# BMS_Slave.net
KiCad netlist of a schematic drawn in Altium Designer
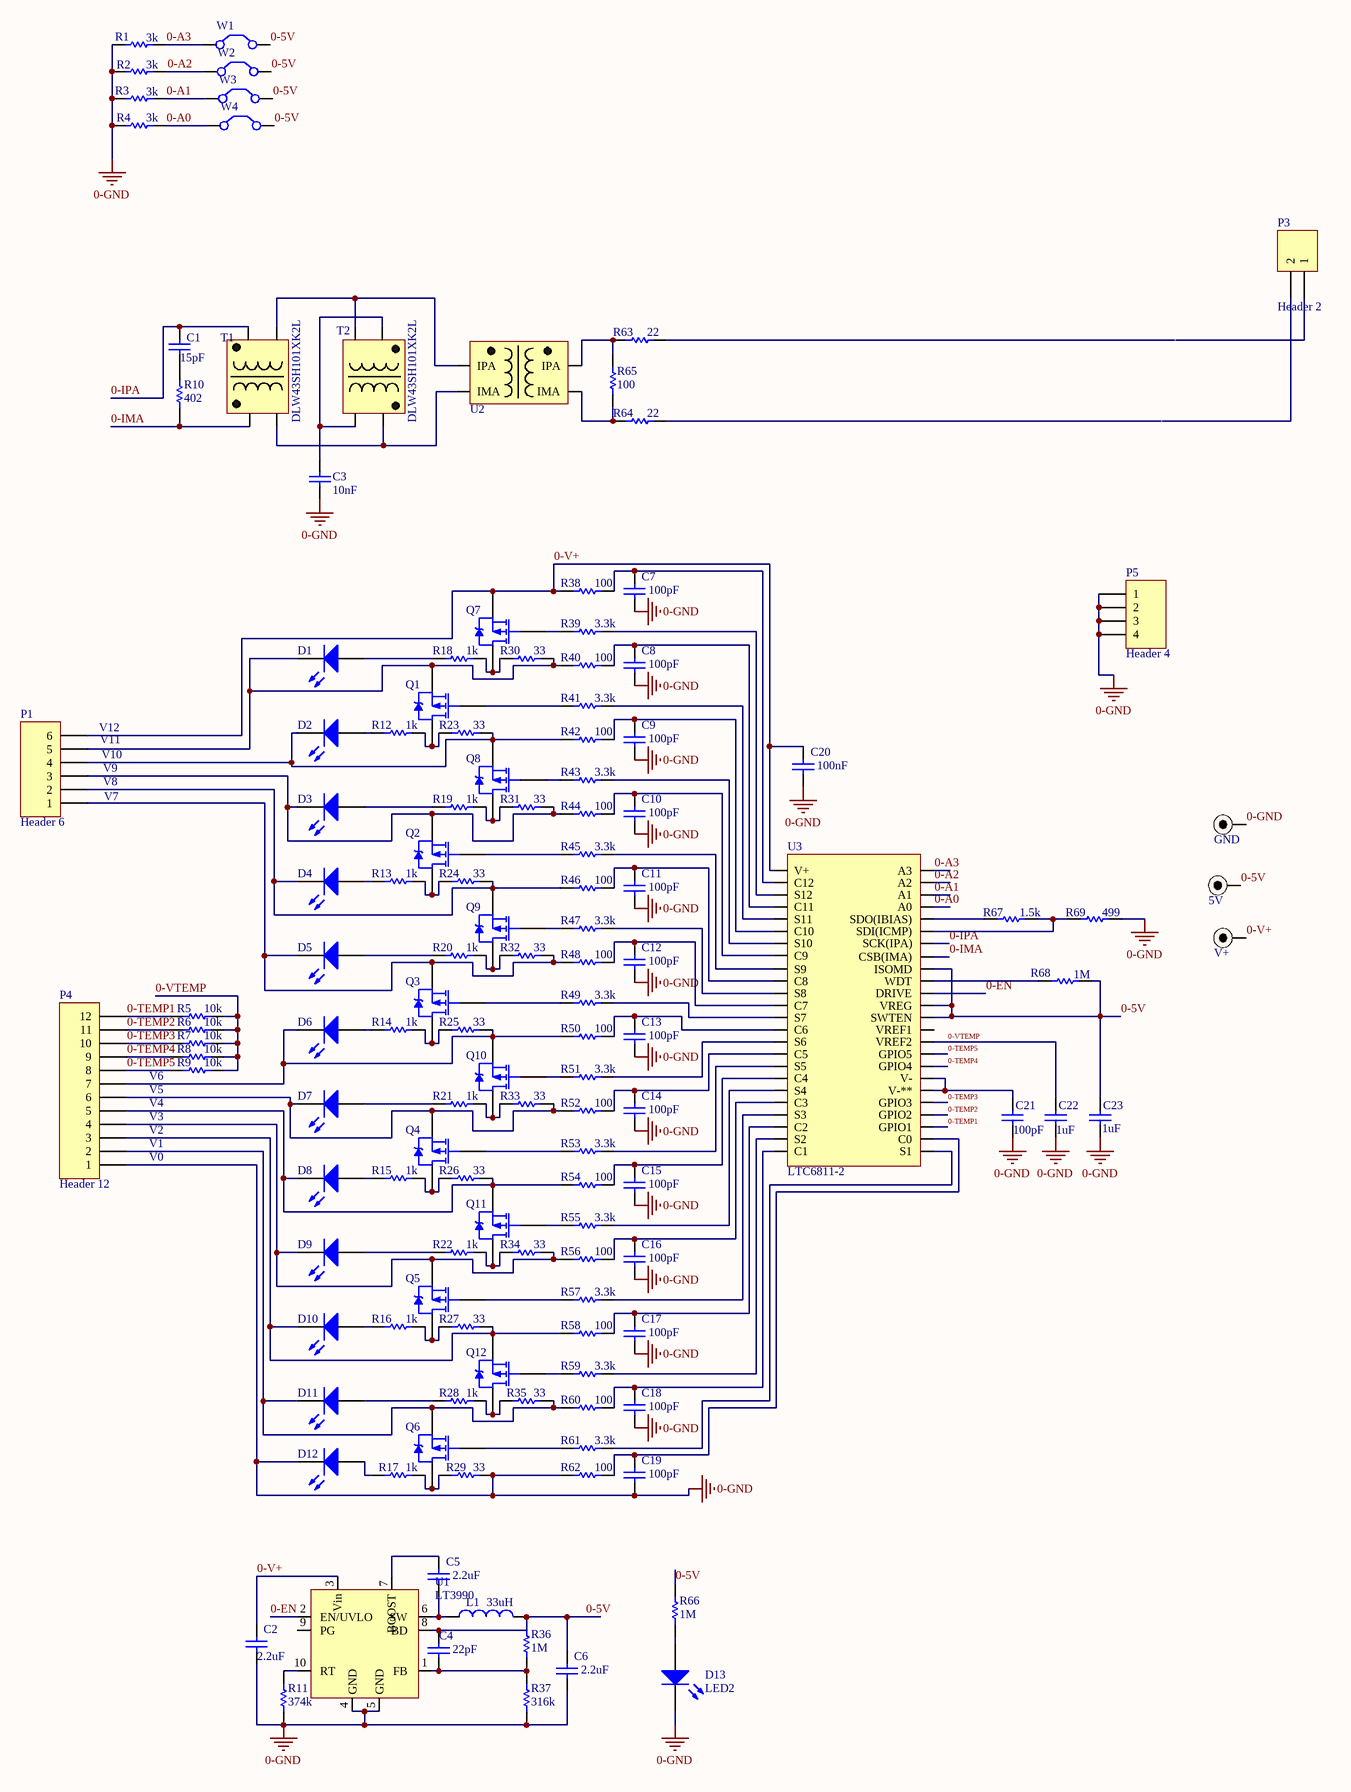
[diagram p0: BMS Slave.SchDoc]

(export (version "E")
  (design (tool "Eeschema 10.0.6"))
  (components
    (comp (ref "5V")
      (value "EXPOSED SOLDER PAD")
      (footprint "TEST PAD")
      (description "testing point")
      (libsource (lib "MFE_temp") (part "EXPOSED SOLDER PAD"))
    )
    (comp (ref "C1")
      (value "15pF")
      (footprint "6-0805_L")
      (description "Capacitor")
      (fields (field (name "Comment") "Cap") (field (name "PUBLISHER") "Altium Limited"))
      (libsource (lib "Miscellaneous Devices") (part "Cap"))
    )
    (comp (ref "C2")
      (value "2.2uF")
      (footprint "6-0805_L")
      (description "Capacitor")
      (fields (field (name "Comment") "Cap") (field (name "PUBLISHER") "Altium Limited"))
      (libsource (lib "Miscellaneous Devices") (part "Cap"))
    )
    (comp (ref "C3")
      (value "10nF")
      (footprint "6-0805_L")
      (description "Capacitor")
      (fields (field (name "Comment") "Cap") (field (name "PUBLISHER") "Altium Limited"))
      (libsource (lib "Miscellaneous Devices") (part "Cap"))
    )
    (comp (ref "C4")
      (value "22pF")
      (footprint "6-0805_L")
      (description "Capacitor")
      (fields (field (name "Comment") "Cap") (field (name "PUBLISHER") "Altium Limited"))
      (libsource (lib "Miscellaneous Devices") (part "Cap"))
    )
    (comp (ref "C5")
      (value "2.2uF")
      (footprint "6-0805_L")
      (description "Capacitor")
      (fields (field (name "Comment") "Cap") (field (name "PUBLISHER") "Altium Limited"))
      (libsource (lib "Miscellaneous Devices") (part "Cap"))
    )
    (comp (ref "C6")
      (value "2.2uF")
      (footprint "6-0805_L")
      (description "Capacitor")
      (fields (field (name "Comment") "Cap") (field (name "PUBLISHER") "Altium Limited"))
      (libsource (lib "Miscellaneous Devices") (part "Cap"))
    )
    (comp (ref "C7")
      (value "100pF")
      (footprint "6-0805_L")
      (description "Capacitor")
      (fields (field (name "Comment") "Cap") (field (name "PUBLISHER") "Altium Limited"))
      (libsource (lib "Miscellaneous Devices") (part "Cap"))
    )
    (comp (ref "C8")
      (value "100pF")
      (footprint "6-0805_L")
      (description "Capacitor")
      (fields (field (name "Comment") "Cap") (field (name "PUBLISHER") "Altium Limited"))
      (libsource (lib "Miscellaneous Devices") (part "Cap"))
    )
    (comp (ref "C9")
      (value "100pF")
      (footprint "6-0805_L")
      (description "Capacitor")
      (fields (field (name "Comment") "Cap") (field (name "PUBLISHER") "Altium Limited"))
      (libsource (lib "Miscellaneous Devices") (part "Cap"))
    )
    (comp (ref "C10")
      (value "100pF")
      (footprint "6-0805_L")
      (description "Capacitor")
      (fields (field (name "Comment") "Cap") (field (name "PUBLISHER") "Altium Limited"))
      (libsource (lib "Miscellaneous Devices") (part "Cap"))
    )
    (comp (ref "C11")
      (value "100pF")
      (footprint "6-0805_L")
      (description "Capacitor")
      (fields (field (name "Comment") "Cap") (field (name "PUBLISHER") "Altium Limited"))
      (libsource (lib "Miscellaneous Devices") (part "Cap"))
    )
    (comp (ref "C12")
      (value "100pF")
      (footprint "6-0805_L")
      (description "Capacitor")
      (fields (field (name "Comment") "Cap") (field (name "PUBLISHER") "Altium Limited"))
      (libsource (lib "Miscellaneous Devices") (part "Cap"))
    )
    (comp (ref "C13")
      (value "100pF")
      (footprint "6-0805_L")
      (description "Capacitor")
      (fields (field (name "Comment") "Cap") (field (name "PUBLISHER") "Altium Limited"))
      (libsource (lib "Miscellaneous Devices") (part "Cap"))
    )
    (comp (ref "C14")
      (value "100pF")
      (footprint "6-0805_L")
      (description "Capacitor")
      (fields (field (name "Comment") "Cap") (field (name "PUBLISHER") "Altium Limited"))
      (libsource (lib "Miscellaneous Devices") (part "Cap"))
    )
    (comp (ref "C15")
      (value "100pF")
      (footprint "6-0805_L")
      (description "Capacitor")
      (fields (field (name "Comment") "Cap") (field (name "PUBLISHER") "Altium Limited"))
      (libsource (lib "Miscellaneous Devices") (part "Cap"))
    )
    (comp (ref "C16")
      (value "100pF")
      (footprint "6-0805_L")
      (description "Capacitor")
      (fields (field (name "Comment") "Cap") (field (name "PUBLISHER") "Altium Limited"))
      (libsource (lib "Miscellaneous Devices") (part "Cap"))
    )
    (comp (ref "C17")
      (value "100pF")
      (footprint "6-0805_L")
      (description "Capacitor")
      (fields (field (name "Comment") "Cap") (field (name "PUBLISHER") "Altium Limited"))
      (libsource (lib "Miscellaneous Devices") (part "Cap"))
    )
    (comp (ref "C18")
      (value "100pF")
      (footprint "6-0805_L")
      (description "Capacitor")
      (fields (field (name "Comment") "Cap") (field (name "PUBLISHER") "Altium Limited"))
      (libsource (lib "Miscellaneous Devices") (part "Cap"))
    )
    (comp (ref "C19")
      (value "100pF")
      (footprint "6-0805_L")
      (description "Capacitor")
      (fields (field (name "Comment") "Cap") (field (name "PUBLISHER") "Altium Limited"))
      (libsource (lib "Miscellaneous Devices") (part "Cap"))
    )
    (comp (ref "C20")
      (value "100nF")
      (footprint "6-0805_L")
      (description "Capacitor")
      (fields (field (name "Comment") "Cap") (field (name "PUBLISHER") "Altium Limited"))
      (libsource (lib "Miscellaneous Devices") (part "Cap"))
    )
    (comp (ref "C21")
      (value "100pF")
      (footprint "6-0805_L")
      (description "Capacitor")
      (fields (field (name "Comment") "Cap") (field (name "PUBLISHER") "Altium Limited"))
      (libsource (lib "Miscellaneous Devices") (part "Cap"))
    )
    (comp (ref "C22")
      (value "1uF")
      (footprint "6-0805_L")
      (description "Capacitor")
      (fields (field (name "Comment") "Cap") (field (name "PUBLISHER") "Altium Limited"))
      (libsource (lib "Miscellaneous Devices") (part "Cap"))
    )
    (comp (ref "C23")
      (value "1uF")
      (footprint "6-0805_L")
      (description "Capacitor")
      (fields (field (name "Comment") "Cap") (field (name "PUBLISHER") "Altium Limited"))
      (libsource (lib "Miscellaneous Devices") (part "Cap"))
    )
    (comp (ref "D1")
      (value "Green LED")
      (footprint "1608[0603]")
      (description "LG L29K-G2J1-24-Z")
      (fields (field (name "PUBLISHER") "Altium Limited"))
      (libsource (lib "Miscellaneous Devices") (part "LED2"))
    )
    (comp (ref "D2")
      (value "Green LED")
      (footprint "1608[0603]")
      (description "LG L29K-G2J1-24-Z")
      (fields (field (name "PUBLISHER") "Altium Limited"))
      (libsource (lib "Miscellaneous Devices") (part "LED2"))
    )
    (comp (ref "D3")
      (value "Green LED")
      (footprint "1608[0603]")
      (description "LG L29K-G2J1-24-Z")
      (fields (field (name "PUBLISHER") "Altium Limited"))
      (libsource (lib "Miscellaneous Devices") (part "LED2"))
    )
    (comp (ref "D4")
      (value "Green LED")
      (footprint "1608[0603]")
      (description "LG L29K-G2J1-24-Z")
      (fields (field (name "PUBLISHER") "Altium Limited"))
      (libsource (lib "Miscellaneous Devices") (part "LED2"))
    )
    (comp (ref "D5")
      (value "Green LED")
      (footprint "1608[0603]")
      (description "LG L29K-G2J1-24-Z")
      (fields (field (name "PUBLISHER") "Altium Limited"))
      (libsource (lib "Miscellaneous Devices") (part "LED2"))
    )
    (comp (ref "D6")
      (value "Green LED")
      (footprint "1608[0603]")
      (description "LG L29K-G2J1-24-Z")
      (fields (field (name "PUBLISHER") "Altium Limited"))
      (libsource (lib "Miscellaneous Devices") (part "LED2"))
    )
    (comp (ref "D7")
      (value "Green LED")
      (footprint "1608[0603]")
      (description "LG L29K-G2J1-24-Z")
      (fields (field (name "PUBLISHER") "Altium Limited"))
      (libsource (lib "Miscellaneous Devices") (part "LED2"))
    )
    (comp (ref "D8")
      (value "Green LED")
      (footprint "1608[0603]")
      (description "LG L29K-G2J1-24-Z")
      (fields (field (name "PUBLISHER") "Altium Limited"))
      (libsource (lib "Miscellaneous Devices") (part "LED2"))
    )
    (comp (ref "D9")
      (value "Green LED")
      (footprint "1608[0603]")
      (description "LG L29K-G2J1-24-Z")
      (fields (field (name "PUBLISHER") "Altium Limited"))
      (libsource (lib "Miscellaneous Devices") (part "LED2"))
    )
    (comp (ref "D10")
      (value "Green LED")
      (footprint "1608[0603]")
      (description "LG L29K-G2J1-24-Z")
      (fields (field (name "PUBLISHER") "Altium Limited"))
      (libsource (lib "Miscellaneous Devices") (part "LED2"))
    )
    (comp (ref "D11")
      (value "Green LED")
      (footprint "1608[0603]")
      (description "LG L29K-G2J1-24-Z")
      (fields (field (name "PUBLISHER") "Altium Limited"))
      (libsource (lib "Miscellaneous Devices") (part "LED2"))
    )
    (comp (ref "D12")
      (value "Green LED")
      (footprint "1608[0603]")
      (description "LG L29K-G2J1-24-Z")
      (fields (field (name "PUBLISHER") "Altium Limited"))
      (libsource (lib "Miscellaneous Devices") (part "LED2"))
    )
    (comp (ref "D13")
      (value "LED2")
      (footprint "3.2X1.6X1.1")
      (description "Typical RED, GREEN, YELLOW, AMBER GaAs LED")
      (fields (field (name "PUBLISHER") "Altium Limited"))
      (libsource (lib "Miscellaneous Devices") (part "LED2"))
    )
    (comp (ref "GND")
      (value "EXPOSED SOLDER PAD")
      (footprint "TEST PAD")
      (description "testing point")
      (libsource (lib "MFE_temp") (part "EXPOSED SOLDER PAD"))
    )
    (comp (ref "L1")
      (value "33uH")
      (footprint "0402-A")
      (description "Inductor")
      (fields (field (name "PUBLISHER") "Altium Limited"))
      (libsource (lib "Miscellaneous Devices") (part "Inductor"))
    )
    (comp (ref "P1")
      (value "Header 6")
      (footprint "HDR2X3_CEN")
      (description "Header, 6-Pin")
      (fields (field (name "PUBLISHER") "Altium Limited"))
      (libsource (lib "Miscellaneous Connectors") (part "Header 6"))
    )
    (comp (ref "P3")
      (value "Header 2")
      (footprint "MOLEX MICROCLASP 2POS RIGHT ANGLE")
      (description "Header, 2-Pin")
      (fields (field (name "PUBLISHER") "Altium Limited"))
      (libsource (lib "Miscellaneous Connectors") (part "Header 2"))
    )
    (comp (ref "P4")
      (value "Header 12")
      (footprint "HDR2X6")
      (description "Header, 12-Pin")
      (fields (field (name "PUBLISHER") "Altium Limited"))
      (libsource (lib "Miscellaneous Connectors") (part "Header 12"))
    )
    (comp (ref "P5")
      (value "Header 4")
      (footprint "HDR2X2")
      (description "Header, 4-Pin")
      (fields (field (name "PUBLISHER") "Altium Limited"))
      (libsource (lib "Miscellaneous Connectors") (part "Header 4"))
    )
    (comp (ref "Q1")
      (value "SI2347DS-T1-GE3")
      (footprint "SOT23-3N")
      (description "MOSFET P-CH 30V 5A SOT-23")
      (fields (field (name "PUBLISHER") "Altium Limited"))
      (libsource (lib "Miscellaneous Devices") (part "PMOS-2"))
    )
    (comp (ref "Q2")
      (value "SI2347DS-T1-GE3")
      (footprint "SOT23-3N")
      (description "MOSFET P-CH 30V 5A SOT-23")
      (fields (field (name "PUBLISHER") "Altium Limited"))
      (libsource (lib "Miscellaneous Devices") (part "PMOS-2"))
    )
    (comp (ref "Q3")
      (value "SI2347DS-T1-GE3")
      (footprint "SOT23-3N")
      (description "MOSFET P-CH 30V 5A SOT-23")
      (fields (field (name "PUBLISHER") "Altium Limited"))
      (libsource (lib "Miscellaneous Devices") (part "PMOS-2"))
    )
    (comp (ref "Q4")
      (value "SI2347DS-T1-GE3")
      (footprint "SOT23-3N")
      (description "MOSFET P-CH 30V 5A SOT-23")
      (fields (field (name "PUBLISHER") "Altium Limited"))
      (libsource (lib "Miscellaneous Devices") (part "PMOS-2"))
    )
    (comp (ref "Q5")
      (value "SI2347DS-T1-GE3")
      (footprint "SOT23-3N")
      (description "MOSFET P-CH 30V 5A SOT-23")
      (fields (field (name "PUBLISHER") "Altium Limited"))
      (libsource (lib "Miscellaneous Devices") (part "PMOS-2"))
    )
    (comp (ref "Q6")
      (value "SI2347DS-T1-GE3")
      (footprint "SOT23-3N")
      (description "MOSFET P-CH 30V 5A SOT-23")
      (fields (field (name "PUBLISHER") "Altium Limited"))
      (libsource (lib "Miscellaneous Devices") (part "PMOS-2"))
    )
    (comp (ref "Q7")
      (value "SI2347DS-T1-GE3")
      (footprint "SOT23-3N")
      (description "MOSFET P-CH 30V 5A SOT-23")
      (fields (field (name "PUBLISHER") "Altium Limited"))
      (libsource (lib "Miscellaneous Devices") (part "PMOS-2"))
    )
    (comp (ref "Q8")
      (value "SI2347DS-T1-GE3")
      (footprint "SOT23-3N")
      (description "MOSFET P-CH 30V 5A SOT-23")
      (fields (field (name "PUBLISHER") "Altium Limited"))
      (libsource (lib "Miscellaneous Devices") (part "PMOS-2"))
    )
    (comp (ref "Q9")
      (value "SI2347DS-T1-GE3")
      (footprint "SOT23-3N")
      (description "MOSFET P-CH 30V 5A SOT-23")
      (fields (field (name "PUBLISHER") "Altium Limited"))
      (libsource (lib "Miscellaneous Devices") (part "PMOS-2"))
    )
    (comp (ref "Q10")
      (value "SI2347DS-T1-GE3")
      (footprint "SOT23-3N")
      (description "MOSFET P-CH 30V 5A SOT-23")
      (fields (field (name "PUBLISHER") "Altium Limited"))
      (libsource (lib "Miscellaneous Devices") (part "PMOS-2"))
    )
    (comp (ref "Q11")
      (value "SI2347DS-T1-GE3")
      (footprint "SOT23-3N")
      (description "MOSFET P-CH 30V 5A SOT-23")
      (fields (field (name "PUBLISHER") "Altium Limited"))
      (libsource (lib "Miscellaneous Devices") (part "PMOS-2"))
    )
    (comp (ref "Q12")
      (value "SI2347DS-T1-GE3")
      (footprint "SOT23-3N")
      (description "MOSFET P-CH 30V 5A SOT-23")
      (fields (field (name "PUBLISHER") "Altium Limited"))
      (libsource (lib "Miscellaneous Devices") (part "PMOS-2"))
    )
    (comp (ref "R1")
      (value "3k")
      (footprint "6-0805_L")
      (description "Resistor")
      (fields (field (name "Comment") "Res1") (field (name "PUBLISHER") "Altium Limited"))
      (libsource (lib "Miscellaneous Devices") (part "Res1"))
    )
    (comp (ref "R2")
      (value "3k")
      (footprint "6-0805_L")
      (description "Resistor")
      (fields (field (name "Comment") "Res1") (field (name "PUBLISHER") "Altium Limited"))
      (libsource (lib "Miscellaneous Devices") (part "Res1"))
    )
    (comp (ref "R3")
      (value "3k")
      (footprint "6-0805_L")
      (description "Resistor")
      (fields (field (name "Comment") "Res1") (field (name "PUBLISHER") "Altium Limited"))
      (libsource (lib "Miscellaneous Devices") (part "Res1"))
    )
    (comp (ref "R4")
      (value "3k")
      (footprint "6-0805_L")
      (description "Resistor")
      (fields (field (name "Comment") "Res1") (field (name "PUBLISHER") "Altium Limited"))
      (libsource (lib "Miscellaneous Devices") (part "Res1"))
    )
    (comp (ref "R5")
      (value "10k")
      (footprint "6-0805_L")
      (description "Resistor")
      (fields (field (name "Comment") "Res1") (field (name "PUBLISHER") "Altium Limited"))
      (libsource (lib "Miscellaneous Devices") (part "Res1"))
    )
    (comp (ref "R6")
      (value "10k")
      (footprint "6-0805_L")
      (description "Resistor")
      (fields (field (name "Comment") "Res1") (field (name "PUBLISHER") "Altium Limited"))
      (libsource (lib "Miscellaneous Devices") (part "Res1"))
    )
    (comp (ref "R7")
      (value "10k")
      (footprint "6-0805_L")
      (description "Resistor")
      (fields (field (name "Comment") "Res1") (field (name "PUBLISHER") "Altium Limited"))
      (libsource (lib "Miscellaneous Devices") (part "Res1"))
    )
    (comp (ref "R8")
      (value "10k")
      (footprint "6-0805_L")
      (description "Resistor")
      (fields (field (name "Comment") "Res1") (field (name "PUBLISHER") "Altium Limited"))
      (libsource (lib "Miscellaneous Devices") (part "Res1"))
    )
    (comp (ref "R9")
      (value "10k")
      (footprint "6-0805_L")
      (description "Resistor")
      (fields (field (name "Comment") "Res1") (field (name "PUBLISHER") "Altium Limited"))
      (libsource (lib "Miscellaneous Devices") (part "Res1"))
    )
    (comp (ref "R10")
      (value "402")
      (footprint "6-0805_L")
      (description "Resistor")
      (fields (field (name "Comment") "Res1") (field (name "PUBLISHER") "Altium Limited"))
      (libsource (lib "Miscellaneous Devices") (part "Res1"))
    )
    (comp (ref "R11")
      (value "374k")
      (footprint "6-0805_L")
      (description "Resistor")
      (fields (field (name "Comment") "Res1") (field (name "PUBLISHER") "Altium Limited"))
      (libsource (lib "Miscellaneous Devices") (part "Res1"))
    )
    (comp (ref "R12")
      (value "1k")
      (footprint "1608[0603]")
      (description "Current Limiting Resistor for Green LED")
      (fields (field (name "Comment") "ESR03EZPJ102") (field (name "PUBLISHER") "Altium Limited"))
      (libsource (lib "Miscellaneous Devices") (part "Res1"))
    )
    (comp (ref "R13")
      (value "1k")
      (footprint "1608[0603]")
      (description "Current Limiting Resistor for Green LED")
      (fields (field (name "Comment") "ESR03EZPJ102") (field (name "PUBLISHER") "Altium Limited"))
      (libsource (lib "Miscellaneous Devices") (part "Res1"))
    )
    (comp (ref "R14")
      (value "1k")
      (footprint "1608[0603]")
      (description "Current Limiting Resistor for Green LED")
      (fields (field (name "Comment") "ESR03EZPJ102") (field (name "PUBLISHER") "Altium Limited"))
      (libsource (lib "Miscellaneous Devices") (part "Res1"))
    )
    (comp (ref "R15")
      (value "1k")
      (footprint "1608[0603]")
      (description "Current Limiting Resistor for Green LED")
      (fields (field (name "Comment") "ESR03EZPJ102") (field (name "PUBLISHER") "Altium Limited"))
      (libsource (lib "Miscellaneous Devices") (part "Res1"))
    )
    (comp (ref "R16")
      (value "1k")
      (footprint "1608[0603]")
      (description "Current Limiting Resistor for Green LED")
      (fields (field (name "Comment") "ESR03EZPJ102") (field (name "PUBLISHER") "Altium Limited"))
      (libsource (lib "Miscellaneous Devices") (part "Res1"))
    )
    (comp (ref "R17")
      (value "1k")
      (footprint "1608[0603]")
      (description "Current Limiting Resistor for Green LED")
      (fields (field (name "Comment") "ESR03EZPJ102") (field (name "PUBLISHER") "Altium Limited"))
      (libsource (lib "Miscellaneous Devices") (part "Res1"))
    )
    (comp (ref "R18")
      (value "1k")
      (footprint "1608[0603]")
      (description "Current Limiting Resistor for Green LED")
      (fields (field (name "Comment") "ESR03EZPJ102") (field (name "PUBLISHER") "Altium Limited"))
      (libsource (lib "Miscellaneous Devices") (part "Res1"))
    )
    (comp (ref "R19")
      (value "1k")
      (footprint "1608[0603]")
      (description "Current Limiting Resistor for Green LED")
      (fields (field (name "Comment") "ESR03EZPJ102") (field (name "PUBLISHER") "Altium Limited"))
      (libsource (lib "Miscellaneous Devices") (part "Res1"))
    )
    (comp (ref "R20")
      (value "1k")
      (footprint "1608[0603]")
      (description "Current Limiting Resistor for Green LED")
      (fields (field (name "Comment") "ESR03EZPJ102") (field (name "PUBLISHER") "Altium Limited"))
      (libsource (lib "Miscellaneous Devices") (part "Res1"))
    )
    (comp (ref "R21")
      (value "1k")
      (footprint "1608[0603]")
      (description "Current Limiting Resistor for Green LED")
      (fields (field (name "Comment") "ESR03EZPJ102") (field (name "PUBLISHER") "Altium Limited"))
      (libsource (lib "Miscellaneous Devices") (part "Res1"))
    )
    (comp (ref "R22")
      (value "1k")
      (footprint "1608[0603]")
      (description "Current Limiting Resistor for Green LED")
      (fields (field (name "Comment") "ESR03EZPJ102") (field (name "PUBLISHER") "Altium Limited"))
      (libsource (lib "Miscellaneous Devices") (part "Res1"))
    )
    (comp (ref "R23")
      (value "33")
      (footprint "RES_4122")
      (description "Resistor")
      (fields (field (name "Comment") "Res1") (field (name "PUBLISHER") "Altium Limited"))
      (libsource (lib "Miscellaneous Devices") (part "Res1"))
    )
    (comp (ref "R24")
      (value "33")
      (footprint "RES_4122")
      (description "Resistor")
      (fields (field (name "Comment") "Res1") (field (name "PUBLISHER") "Altium Limited"))
      (libsource (lib "Miscellaneous Devices") (part "Res1"))
    )
    (comp (ref "R25")
      (value "33")
      (footprint "RES_4122")
      (description "Resistor")
      (fields (field (name "Comment") "Res1") (field (name "PUBLISHER") "Altium Limited"))
      (libsource (lib "Miscellaneous Devices") (part "Res1"))
    )
    (comp (ref "R26")
      (value "33")
      (footprint "RES_4122")
      (description "Resistor")
      (fields (field (name "Comment") "Res1") (field (name "PUBLISHER") "Altium Limited"))
      (libsource (lib "Miscellaneous Devices") (part "Res1"))
    )
    (comp (ref "R27")
      (value "33")
      (footprint "RES_4122")
      (description "Resistor")
      (fields (field (name "Comment") "Res1") (field (name "PUBLISHER") "Altium Limited"))
      (libsource (lib "Miscellaneous Devices") (part "Res1"))
    )
    (comp (ref "R28")
      (value "1k")
      (footprint "1608[0603]")
      (description "Current Limiting Resistor for Green LED")
      (fields (field (name "Comment") "ESR03EZPJ102") (field (name "PUBLISHER") "Altium Limited"))
      (libsource (lib "Miscellaneous Devices") (part "Res1"))
    )
    (comp (ref "R29")
      (value "33")
      (footprint "RES_4122")
      (description "Resistor")
      (fields (field (name "Comment") "Res1") (field (name "PUBLISHER") "Altium Limited"))
      (libsource (lib "Miscellaneous Devices") (part "Res1"))
    )
    (comp (ref "R30")
      (value "33")
      (footprint "RES_4122")
      (description "Resistor")
      (fields (field (name "Comment") "Res1") (field (name "PUBLISHER") "Altium Limited"))
      (libsource (lib "Miscellaneous Devices") (part "Res1"))
    )
    (comp (ref "R31")
      (value "33")
      (footprint "RES_4122")
      (description "Resistor")
      (fields (field (name "Comment") "Res1") (field (name "PUBLISHER") "Altium Limited"))
      (libsource (lib "Miscellaneous Devices") (part "Res1"))
    )
    (comp (ref "R32")
      (value "33")
      (footprint "RES_4122")
      (description "Resistor")
      (fields (field (name "Comment") "Res1") (field (name "PUBLISHER") "Altium Limited"))
      (libsource (lib "Miscellaneous Devices") (part "Res1"))
    )
    (comp (ref "R33")
      (value "33")
      (footprint "RES_4122")
      (description "Resistor")
      (fields (field (name "Comment") "Res1") (field (name "PUBLISHER") "Altium Limited"))
      (libsource (lib "Miscellaneous Devices") (part "Res1"))
    )
    (comp (ref "R34")
      (value "33")
      (footprint "RES_4122")
      (description "Resistor")
      (fields (field (name "Comment") "Res1") (field (name "PUBLISHER") "Altium Limited"))
      (libsource (lib "Miscellaneous Devices") (part "Res1"))
    )
    (comp (ref "R35")
      (value "33")
      (footprint "RES_4122")
      (description "Resistor")
      (fields (field (name "Comment") "Res1") (field (name "PUBLISHER") "Altium Limited"))
      (libsource (lib "Miscellaneous Devices") (part "Res1"))
    )
    (comp (ref "R36")
      (value "1M")
      (footprint "6-0805_L")
      (description "Resistor")
      (fields (field (name "Comment") "Res1") (field (name "PUBLISHER") "Altium Limited"))
      (libsource (lib "Miscellaneous Devices") (part "Res1"))
    )
    (comp (ref "R37")
      (value "316k")
      (footprint "6-0805_L")
      (description "Resistor")
      (fields (field (name "Comment") "Res1") (field (name "PUBLISHER") "Altium Limited"))
      (libsource (lib "Miscellaneous Devices") (part "Res1"))
    )
    (comp (ref "R38")
      (value "100")
      (footprint "6-0805_L")
      (description "Resistor")
      (fields (field (name "Comment") "Res1") (field (name "PUBLISHER") "Altium Limited"))
      (libsource (lib "Miscellaneous Devices") (part "Res1"))
    )
    (comp (ref "R39")
      (value "3.3k")
      (footprint "6-0805_L")
      (description "Resistor")
      (fields (field (name "Comment") "Res1") (field (name "PUBLISHER") "Altium Limited"))
      (libsource (lib "Miscellaneous Devices") (part "Res1"))
    )
    (comp (ref "R40")
      (value "100")
      (footprint "6-0805_L")
      (description "Resistor")
      (fields (field (name "Comment") "Res1") (field (name "PUBLISHER") "Altium Limited"))
      (libsource (lib "Miscellaneous Devices") (part "Res1"))
    )
    (comp (ref "R41")
      (value "3.3k")
      (footprint "6-0805_L")
      (description "Resistor")
      (fields (field (name "Comment") "Res1") (field (name "PUBLISHER") "Altium Limited"))
      (libsource (lib "Miscellaneous Devices") (part "Res1"))
    )
    (comp (ref "R42")
      (value "100")
      (footprint "6-0805_L")
      (description "Resistor")
      (fields (field (name "Comment") "Res1") (field (name "PUBLISHER") "Altium Limited"))
      (libsource (lib "Miscellaneous Devices") (part "Res1"))
    )
    (comp (ref "R43")
      (value "3.3k")
      (footprint "6-0805_L")
      (description "Resistor")
      (fields (field (name "Comment") "Res1") (field (name "PUBLISHER") "Altium Limited"))
      (libsource (lib "Miscellaneous Devices") (part "Res1"))
    )
    (comp (ref "R44")
      (value "100")
      (footprint "6-0805_L")
      (description "Resistor")
      (fields (field (name "Comment") "Res1") (field (name "PUBLISHER") "Altium Limited"))
      (libsource (lib "Miscellaneous Devices") (part "Res1"))
    )
    (comp (ref "R45")
      (value "3.3k")
      (footprint "6-0805_L")
      (description "Resistor")
      (fields (field (name "Comment") "Res1") (field (name "PUBLISHER") "Altium Limited"))
      (libsource (lib "Miscellaneous Devices") (part "Res1"))
    )
    (comp (ref "R46")
      (value "100")
      (footprint "6-0805_L")
      (description "Resistor")
      (fields (field (name "Comment") "Res1") (field (name "PUBLISHER") "Altium Limited"))
      (libsource (lib "Miscellaneous Devices") (part "Res1"))
    )
    (comp (ref "R47")
      (value "3.3k")
      (footprint "6-0805_L")
      (description "Resistor")
      (fields (field (name "Comment") "Res1") (field (name "PUBLISHER") "Altium Limited"))
      (libsource (lib "Miscellaneous Devices") (part "Res1"))
    )
    (comp (ref "R48")
      (value "100")
      (footprint "6-0805_L")
      (description "Resistor")
      (fields (field (name "Comment") "Res1") (field (name "PUBLISHER") "Altium Limited"))
      (libsource (lib "Miscellaneous Devices") (part "Res1"))
    )
    (comp (ref "R49")
      (value "3.3k")
      (footprint "6-0805_L")
      (description "Resistor")
      (fields (field (name "Comment") "Res1") (field (name "PUBLISHER") "Altium Limited"))
      (libsource (lib "Miscellaneous Devices") (part "Res1"))
    )
    (comp (ref "R50")
      (value "100")
      (footprint "6-0805_L")
      (description "Resistor")
      (fields (field (name "Comment") "Res1") (field (name "PUBLISHER") "Altium Limited"))
      (libsource (lib "Miscellaneous Devices") (part "Res1"))
    )
    (comp (ref "R51")
      (value "3.3k")
      (footprint "6-0805_L")
      (description "Resistor")
      (fields (field (name "Comment") "Res1") (field (name "PUBLISHER") "Altium Limited"))
      (libsource (lib "Miscellaneous Devices") (part "Res1"))
    )
    (comp (ref "R52")
      (value "100")
      (footprint "6-0805_L")
      (description "Resistor")
      (fields (field (name "Comment") "Res1") (field (name "PUBLISHER") "Altium Limited"))
      (libsource (lib "Miscellaneous Devices") (part "Res1"))
    )
    (comp (ref "R53")
      (value "3.3k")
      (footprint "6-0805_L")
      (description "Resistor")
      (fields (field (name "Comment") "Res1") (field (name "PUBLISHER") "Altium Limited"))
      (libsource (lib "Miscellaneous Devices") (part "Res1"))
    )
    (comp (ref "R54")
      (value "100")
      (footprint "6-0805_L")
      (description "Resistor")
      (fields (field (name "Comment") "Res1") (field (name "PUBLISHER") "Altium Limited"))
      (libsource (lib "Miscellaneous Devices") (part "Res1"))
    )
    (comp (ref "R55")
      (value "3.3k")
      (footprint "6-0805_L")
      (description "Resistor")
      (fields (field (name "Comment") "Res1") (field (name "PUBLISHER") "Altium Limited"))
      (libsource (lib "Miscellaneous Devices") (part "Res1"))
    )
    (comp (ref "R56")
      (value "100")
      (footprint "6-0805_L")
      (description "Resistor")
      (fields (field (name "Comment") "Res1") (field (name "PUBLISHER") "Altium Limited"))
      (libsource (lib "Miscellaneous Devices") (part "Res1"))
    )
    (comp (ref "R57")
      (value "3.3k")
      (footprint "6-0805_L")
      (description "Resistor")
      (fields (field (name "Comment") "Res1") (field (name "PUBLISHER") "Altium Limited"))
      (libsource (lib "Miscellaneous Devices") (part "Res1"))
    )
    (comp (ref "R58")
      (value "100")
      (footprint "6-0805_L")
      (description "Resistor")
      (fields (field (name "Comment") "Res1") (field (name "PUBLISHER") "Altium Limited"))
      (libsource (lib "Miscellaneous Devices") (part "Res1"))
    )
    (comp (ref "R59")
      (value "3.3k")
      (footprint "6-0805_L")
      (description "Resistor")
      (fields (field (name "Comment") "Res1") (field (name "PUBLISHER") "Altium Limited"))
      (libsource (lib "Miscellaneous Devices") (part "Res1"))
    )
    (comp (ref "R60")
      (value "100")
      (footprint "6-0805_L")
      (description "Resistor")
      (fields (field (name "Comment") "Res1") (field (name "PUBLISHER") "Altium Limited"))
      (libsource (lib "Miscellaneous Devices") (part "Res1"))
    )
    (comp (ref "R61")
      (value "3.3k")
      (footprint "6-0805_L")
      (description "Resistor")
      (fields (field (name "Comment") "Res1") (field (name "PUBLISHER") "Altium Limited"))
      (libsource (lib "Miscellaneous Devices") (part "Res1"))
    )
    (comp (ref "R62")
      (value "100")
      (footprint "6-0805_L")
      (description "Resistor")
      (fields (field (name "Comment") "Res1") (field (name "PUBLISHER") "Altium Limited"))
      (libsource (lib "Miscellaneous Devices") (part "Res1"))
    )
    (comp (ref "R63")
      (value "22")
      (footprint "6-0805_L")
      (description "Resistor")
      (fields (field (name "Comment") "Res1") (field (name "PUBLISHER") "Altium Limited"))
      (libsource (lib "Miscellaneous Devices") (part "Res1"))
    )
    (comp (ref "R64")
      (value "22")
      (footprint "6-0805_L")
      (description "Resistor")
      (fields (field (name "Comment") "Res1") (field (name "PUBLISHER") "Altium Limited"))
      (libsource (lib "Miscellaneous Devices") (part "Res1"))
    )
    (comp (ref "R65")
      (value "100")
      (footprint "6-0805_L")
      (description "Resistor")
      (fields (field (name "Comment") "Res1") (field (name "PUBLISHER") "Altium Limited"))
      (libsource (lib "Miscellaneous Devices") (part "Res1"))
    )
    (comp (ref "R66")
      (value "1M")
      (footprint "6-0805_L")
      (description "Resistor")
      (fields (field (name "Comment") "Res1") (field (name "PUBLISHER") "Altium Limited"))
      (libsource (lib "Miscellaneous Devices") (part "Res1"))
    )
    (comp (ref "R67")
      (value "1.5k")
      (footprint "6-0805_L")
      (description "Resistor")
      (fields (field (name "Comment") "Res1") (field (name "PUBLISHER") "Altium Limited"))
      (libsource (lib "Miscellaneous Devices") (part "Res1"))
    )
    (comp (ref "R68")
      (value "1M")
      (footprint "6-0805_L")
      (description "Resistor")
      (fields (field (name "Comment") "Res1") (field (name "PUBLISHER") "Altium Limited"))
      (libsource (lib "Miscellaneous Devices") (part "Res1"))
    )
    (comp (ref "R69")
      (value "499")
      (footprint "6-0805_L")
      (description "Resistor")
      (fields (field (name "Comment") "Res1") (field (name "PUBLISHER") "Altium Limited"))
      (libsource (lib "Miscellaneous Devices") (part "Res1"))
    )
    (comp (ref "T1")
      (value "DLW43SH101XK2L")
      (footprint "DLW43SH101XK2L")
      (description "100uH CMC")
      (libsource (lib "") (part "DLW43SH101XK2L_1"))
    )
    (comp (ref "T2")
      (value "DLW43SH101XK2L")
      (footprint "DLW43SH101XK2L")
      (description "100uH CMC")
      (libsource (lib "MFE_temp") (part "DLW43SH101XK2L"))
    )
    (comp (ref "U1")
      (value "LT3990")
      (footprint "LT3990")
      (description "LT3990 62V, 350mA Step-Down Regulator")
      (libsource (lib "MFE_temp") (part "LT3990"))
    )
    (comp (ref "U2")
      (value "PE68386")
      (footprint "PE68386")
      (description "1:1 isolation transformer")
      (libsource (lib "MFE_temp") (part "PE68386"))
    )
    (comp (ref "U3")
      (value "LTC6811-2")
      (footprint "SSOP50P780X200-48N")
      (description "12-cell battery management chip")
      (libsource (lib "MFE_temp") (part "LTC6811-2"))
    )
    (comp (ref "V+")
      (value "EXPOSED SOLDER PAD")
      (footprint "TEST PAD")
      (description "testing point")
      (libsource (lib "MFE_temp") (part "EXPOSED SOLDER PAD"))
    )
    (comp (ref "W1")
      (value "Jumper")
      (footprint "jumper")
      (description "Jumper Wire")
      (fields (field (name "PUBLISHER") "Altium Limited"))
      (libsource (lib "Miscellaneous Devices") (part "Jumper"))
    )
    (comp (ref "W2")
      (value "Jumper")
      (footprint "jumper")
      (description "Jumper Wire")
      (fields (field (name "PUBLISHER") "Altium Limited"))
      (libsource (lib "Miscellaneous Devices") (part "Jumper"))
    )
    (comp (ref "W3")
      (value "Jumper")
      (footprint "jumper")
      (description "Jumper Wire")
      (fields (field (name "PUBLISHER") "Altium Limited"))
      (libsource (lib "Miscellaneous Devices") (part "Jumper"))
    )
    (comp (ref "W4")
      (value "Jumper")
      (footprint "jumper")
      (description "Jumper Wire")
      (fields (field (name "PUBLISHER") "Altium Limited"))
      (libsource (lib "Miscellaneous Devices") (part "Jumper"))
    )
  )
  (nets
    (net (code "1") (name "/0-5V") (class "Default")
      (node (ref "5V") (pin "1") (pinfunction "PAD_1") (pintype "passive"))
      (node (ref "C23") (pin "2") (pinfunction "2_2") (pintype "passive"))
      (node (ref "C4") (pin "2") (pinfunction "2_2") (pintype "passive"))
      (node (ref "C6") (pin "2") (pinfunction "2_2") (pintype "passive"))
      (node (ref "L1") (pin "2") (pinfunction "2_2") (pintype "passive"))
      (node (ref "R36") (pin "2") (pinfunction "2_2") (pintype "passive"))
      (node (ref "R66") (pin "1") (pinfunction "1_1") (pintype "passive"))
      (node (ref "R68") (pin "2") (pinfunction "2_2") (pintype "passive"))
      (node (ref "U1") (pin "8") (pinfunction "BD_8") (pintype "passive"))
      (node (ref "U3") (pin "36") (pinfunction "SWTEN_36") (pintype "passive"))
      (node (ref "U3") (pin "37") (pinfunction "VREG_37") (pintype "passive"))
      (node (ref "U3") (pin "40") (pinfunction "ISOMD_40") (pintype "passive"))
      (node (ref "W1") (pin "2") (pinfunction "C2_2") (pintype "passive"))
      (node (ref "W2") (pin "2") (pinfunction "C2_2") (pintype "passive"))
      (node (ref "W3") (pin "2") (pinfunction "C2_2") (pintype "passive"))
      (node (ref "W4") (pin "2") (pinfunction "C2_2") (pintype "passive"))
    )
    (net (code "2") (name "/0-A0") (class "Default")
      (node (ref "R4") (pin "2") (pinfunction "2_2") (pintype "passive"))
      (node (ref "U3") (pin "45") (pinfunction "A0_45") (pintype "passive"))
      (node (ref "W4") (pin "1") (pinfunction "C1_1") (pintype "passive"))
    )
    (net (code "3") (name "/0-A1") (class "Default")
      (node (ref "R3") (pin "2") (pinfunction "2_2") (pintype "passive"))
      (node (ref "U3") (pin "46") (pinfunction "A1_46") (pintype "passive"))
      (node (ref "W3") (pin "1") (pinfunction "C1_1") (pintype "passive"))
    )
    (net (code "4") (name "/0-A2") (class "Default")
      (node (ref "R2") (pin "2") (pinfunction "2_2") (pintype "passive"))
      (node (ref "U3") (pin "47") (pinfunction "A2_47") (pintype "passive"))
      (node (ref "W2") (pin "1") (pinfunction "C1_1") (pintype "passive"))
    )
    (net (code "5") (name "/0-A3") (class "Default")
      (node (ref "R1") (pin "2") (pinfunction "2_2") (pintype "passive"))
      (node (ref "U3") (pin "48") (pinfunction "A3_48") (pintype "passive"))
      (node (ref "W1") (pin "1") (pinfunction "C1_1") (pintype "passive"))
    )
    (net (code "6") (name "/0-EN") (class "Default")
      (node (ref "U1") (pin "2") (pinfunction "EN/UVLO_2") (pintype "passive"))
      (node (ref "U3") (pin "38") (pinfunction "DRIVE_38") (pintype "passive"))
    )
    (net (code "7") (name "/0-IMA") (class "Default")
      (node (ref "R10") (pin "1") (pinfunction "1_1") (pintype "passive"))
      (node (ref "T1") (pin "1") (pintype "passive"))
      (node (ref "U3") (pin "41") (pinfunction "CSB(IMA)_41") (pintype "passive"))
    )
    (net (code "8") (name "/0-IPA") (class "Default")
      (node (ref "C1") (pin "2") (pinfunction "2_2") (pintype "passive"))
      (node (ref "T1") (pin "4") (pintype "passive"))
      (node (ref "U3") (pin "42") (pinfunction "SCK(IPA)_42") (pintype "passive"))
    )
    (net (code "9") (name "/0-TEMP1") (class "Default")
      (node (ref "P4") (pin "10") (pinfunction "12_10") (pintype "passive"))
      (node (ref "R5") (pin "2") (pinfunction "2_2") (pintype "passive"))
      (node (ref "U3") (pin "27") (pinfunction "GPIO1_27") (pintype "passive"))
    )
    (net (code "10") (name "/0-TEMP2") (class "Default")
      (node (ref "P4") (pin "12") (pinfunction "11_12") (pintype "passive"))
      (node (ref "R6") (pin "2") (pinfunction "2_2") (pintype "passive"))
      (node (ref "U3") (pin "28") (pinfunction "GPIO2_28") (pintype "passive"))
    )
    (net (code "11") (name "/0-TEMP3") (class "Default")
      (node (ref "P4") (pin "11") (pinfunction "10_11") (pintype "passive"))
      (node (ref "R7") (pin "2") (pinfunction "2_2") (pintype "passive"))
      (node (ref "U3") (pin "29") (pinfunction "GPIO3_29") (pintype "passive"))
    )
    (net (code "12") (name "/0-TEMP4") (class "Default")
      (node (ref "P4") (pin "9") (pinfunction "9_9") (pintype "passive"))
      (node (ref "R8") (pin "2") (pinfunction "2_2") (pintype "passive"))
      (node (ref "U3") (pin "32") (pinfunction "GPIO4_32") (pintype "passive"))
    )
    (net (code "13") (name "/0-TEMP5") (class "Default")
      (node (ref "P4") (pin "7") (pinfunction "8_7") (pintype "passive"))
      (node (ref "R9") (pin "2") (pinfunction "2_2") (pintype "passive"))
      (node (ref "U3") (pin "33") (pinfunction "GPIO5_33") (pintype "passive"))
    )
    (net (code "14") (name "/0-V+") (class "Default")
      (node (ref "C2") (pin "2") (pinfunction "2_2") (pintype "passive"))
      (node (ref "C20") (pin "2") (pinfunction "2_2") (pintype "passive"))
      (node (ref "P1") (pin "6") (pinfunction "6_6") (pintype "passive"))
      (node (ref "Q7") (pin "3") (pinfunction "S_3") (pintype "passive"))
      (node (ref "R38") (pin "2") (pinfunction "2_2") (pintype "passive"))
      (node (ref "U1") (pin "3") (pinfunction "Vin_3") (pintype "passive"))
      (node (ref "U3") (pin "1") (pinfunction "V+_1") (pintype "passive"))
      (node (ref "V+") (pin "1") (pinfunction "PAD_1") (pintype "passive"))
    )
    (net (code "15") (name "/0-VTEMP") (class "Default")
      (node (ref "C22") (pin "1") (pinfunction "1_1") (pintype "passive"))
      (node (ref "R5") (pin "1") (pinfunction "1_1") (pintype "passive"))
      (node (ref "R6") (pin "1") (pinfunction "1_1") (pintype "passive"))
      (node (ref "R7") (pin "1") (pinfunction "1_1") (pintype "passive"))
      (node (ref "R8") (pin "1") (pinfunction "1_1") (pintype "passive"))
      (node (ref "R9") (pin "1") (pinfunction "1_1") (pintype "passive"))
      (node (ref "U3") (pin "34") (pinfunction "VREF2_34") (pintype "passive"))
    )
    (net (code "16") (name "0-GND") (class "Default")
      (node (ref "C10") (pin "1") (pinfunction "1_1") (pintype "passive"))
      (node (ref "C11") (pin "1") (pinfunction "1_1") (pintype "passive"))
      (node (ref "C12") (pin "1") (pinfunction "1_1") (pintype "passive"))
      (node (ref "C13") (pin "1") (pinfunction "1_1") (pintype "passive"))
      (node (ref "C14") (pin "1") (pinfunction "1_1") (pintype "passive"))
      (node (ref "C15") (pin "1") (pinfunction "1_1") (pintype "passive"))
      (node (ref "C16") (pin "1") (pinfunction "1_1") (pintype "passive"))
      (node (ref "C17") (pin "1") (pinfunction "1_1") (pintype "passive"))
      (node (ref "C18") (pin "1") (pinfunction "1_1") (pintype "passive"))
      (node (ref "C19") (pin "1") (pinfunction "1_1") (pintype "passive"))
      (node (ref "C2") (pin "1") (pinfunction "1_1") (pintype "passive"))
      (node (ref "C20") (pin "1") (pinfunction "1_1") (pintype "passive"))
      (node (ref "C21") (pin "1") (pinfunction "1_1") (pintype "passive"))
      (node (ref "C22") (pin "2") (pinfunction "2_2") (pintype "passive"))
      (node (ref "C23") (pin "1") (pinfunction "1_1") (pintype "passive"))
      (node (ref "C3") (pin "2") (pinfunction "2_2") (pintype "passive"))
      (node (ref "C6") (pin "1") (pinfunction "1_1") (pintype "passive"))
      (node (ref "C7") (pin "1") (pinfunction "1_1") (pintype "passive"))
      (node (ref "C8") (pin "1") (pinfunction "1_1") (pintype "passive"))
      (node (ref "C9") (pin "1") (pinfunction "1_1") (pintype "passive"))
      (node (ref "D12") (pin "2") (pinfunction "K_2") (pintype "passive"))
      (node (ref "D13") (pin "2") (pinfunction "K_2") (pintype "passive"))
      (node (ref "GND") (pin "1") (pinfunction "PAD_1") (pintype "passive"))
      (node (ref "P4") (pin "8") (pinfunction "1_8") (pintype "passive"))
      (node (ref "P5") (pin "1") (pinfunction "1_1") (pintype "passive"))
      (node (ref "P5") (pin "2") (pinfunction "2_2") (pintype "passive"))
      (node (ref "P5") (pin "3") (pinfunction "3_3") (pintype "passive"))
      (node (ref "P5") (pin "4") (pinfunction "4_4") (pintype "passive"))
      (node (ref "R1") (pin "1") (pinfunction "1_1") (pintype "passive"))
      (node (ref "R11") (pin "1") (pinfunction "1_1") (pintype "passive"))
      (node (ref "R2") (pin "1") (pinfunction "1_1") (pintype "passive"))
      (node (ref "R29") (pin "1") (pinfunction "1_1") (pintype "passive"))
      (node (ref "R3") (pin "1") (pinfunction "1_1") (pintype "passive"))
      (node (ref "R37") (pin "1") (pinfunction "1_1") (pintype "passive"))
      (node (ref "R4") (pin "1") (pinfunction "1_1") (pintype "passive"))
      (node (ref "R62") (pin "2") (pinfunction "2_2") (pintype "passive"))
      (node (ref "R69") (pin "2") (pinfunction "2_2") (pintype "passive"))
      (node (ref "U1") (pin "4") (pinfunction "GND_4") (pintype "passive"))
      (node (ref "U1") (pin "5") (pinfunction "GND_5") (pintype "passive"))
    )
    (net (code "17") (name "Net-(C1-Pad1)") (class "Default")
      (node (ref "C1") (pin "1") (pinfunction "1_1") (pintype "passive"))
      (node (ref "R10") (pin "2") (pinfunction "2_2") (pintype "passive"))
    )
    (net (code "18") (name "Net-(C3-Pad1)") (class "Default")
      (node (ref "C3") (pin "1") (pinfunction "1_1") (pintype "passive"))
      (node (ref "T2") (pin "1") (pintype "passive"))
      (node (ref "T2") (pin "3") (pintype "passive"))
    )
    (net (code "19") (name "Net-(D1-A)") (class "Default")
      (node (ref "D1") (pin "1") (pinfunction "A_1") (pintype "passive"))
      (node (ref "R18") (pin "1") (pinfunction "1_1") (pintype "passive"))
    )
    (net (code "20") (name "Net-(D1-K)") (class "Default")
      (node (ref "D1") (pin "2") (pinfunction "K_2") (pintype "passive"))
      (node (ref "P1") (pin "3") (pinfunction "5_3") (pintype "passive"))
      (node (ref "Q1") (pin "3") (pinfunction "S_3") (pintype "passive"))
      (node (ref "R30") (pin "1") (pinfunction "1_1") (pintype "passive"))
      (node (ref "R40") (pin "2") (pinfunction "2_2") (pintype "passive"))
    )
    (net (code "21") (name "Net-(D2-A)") (class "Default")
      (node (ref "D2") (pin "1") (pinfunction "A_1") (pintype "passive"))
      (node (ref "R12") (pin "2") (pinfunction "2_2") (pintype "passive"))
    )
    (net (code "22") (name "Net-(D2-K)") (class "Default")
      (node (ref "D2") (pin "2") (pinfunction "K_2") (pintype "passive"))
      (node (ref "P1") (pin "2") (pinfunction "4_2") (pintype "passive"))
      (node (ref "Q8") (pin "3") (pinfunction "S_3") (pintype "passive"))
      (node (ref "R23") (pin "1") (pinfunction "1_1") (pintype "passive"))
      (node (ref "R42") (pin "2") (pinfunction "2_2") (pintype "passive"))
    )
    (net (code "23") (name "Net-(D3-A)") (class "Default")
      (node (ref "D3") (pin "1") (pinfunction "A_1") (pintype "passive"))
      (node (ref "R19") (pin "1") (pinfunction "1_1") (pintype "passive"))
    )
    (net (code "24") (name "Net-(D3-K)") (class "Default")
      (node (ref "D3") (pin "2") (pinfunction "K_2") (pintype "passive"))
      (node (ref "P1") (pin "1") (pinfunction "3_1") (pintype "passive"))
      (node (ref "Q2") (pin "3") (pinfunction "S_3") (pintype "passive"))
      (node (ref "R31") (pin "1") (pinfunction "1_1") (pintype "passive"))
      (node (ref "R44") (pin "2") (pinfunction "2_2") (pintype "passive"))
    )
    (net (code "25") (name "Net-(D4-A)") (class "Default")
      (node (ref "D4") (pin "1") (pinfunction "A_1") (pintype "passive"))
      (node (ref "R13") (pin "1") (pinfunction "1_1") (pintype "passive"))
    )
    (net (code "26") (name "Net-(D4-K)") (class "Default")
      (node (ref "D4") (pin "2") (pinfunction "K_2") (pintype "passive"))
      (node (ref "P1") (pin "4") (pinfunction "2_4") (pintype "passive"))
      (node (ref "Q9") (pin "3") (pinfunction "S_3") (pintype "passive"))
      (node (ref "R24") (pin "1") (pinfunction "1_1") (pintype "passive"))
      (node (ref "R46") (pin "2") (pinfunction "2_2") (pintype "passive"))
    )
    (net (code "27") (name "Net-(D5-A)") (class "Default")
      (node (ref "D5") (pin "1") (pinfunction "A_1") (pintype "passive"))
      (node (ref "R20") (pin "1") (pinfunction "1_1") (pintype "passive"))
    )
    (net (code "28") (name "Net-(D5-K)") (class "Default")
      (node (ref "D5") (pin "2") (pinfunction "K_2") (pintype "passive"))
      (node (ref "P1") (pin "5") (pinfunction "1_5") (pintype "passive"))
      (node (ref "Q3") (pin "3") (pinfunction "S_3") (pintype "passive"))
      (node (ref "R32") (pin "1") (pinfunction "1_1") (pintype "passive"))
      (node (ref "R48") (pin "2") (pinfunction "2_2") (pintype "passive"))
    )
    (net (code "29") (name "Net-(D6-A)") (class "Default")
      (node (ref "D6") (pin "1") (pinfunction "A_1") (pintype "passive"))
      (node (ref "R14") (pin "1") (pinfunction "1_1") (pintype "passive"))
    )
    (net (code "30") (name "Net-(D6-K)") (class "Default")
      (node (ref "D6") (pin "2") (pinfunction "K_2") (pintype "passive"))
      (node (ref "P4") (pin "5") (pinfunction "7_5") (pintype "passive"))
      (node (ref "Q10") (pin "3") (pinfunction "S_3") (pintype "passive"))
      (node (ref "R25") (pin "1") (pinfunction "1_1") (pintype "passive"))
      (node (ref "R50") (pin "2") (pinfunction "2_2") (pintype "passive"))
    )
    (net (code "31") (name "Net-(D7-A)") (class "Default")
      (node (ref "D7") (pin "1") (pinfunction "A_1") (pintype "passive"))
      (node (ref "R21") (pin "1") (pinfunction "1_1") (pintype "passive"))
    )
    (net (code "32") (name "Net-(D7-K)") (class "Default")
      (node (ref "D7") (pin "2") (pinfunction "K_2") (pintype "passive"))
      (node (ref "P4") (pin "3") (pinfunction "6_3") (pintype "passive"))
      (node (ref "Q4") (pin "3") (pinfunction "S_3") (pintype "passive"))
      (node (ref "R33") (pin "1") (pinfunction "1_1") (pintype "passive"))
      (node (ref "R52") (pin "2") (pinfunction "2_2") (pintype "passive"))
    )
    (net (code "33") (name "Net-(D8-A)") (class "Default")
      (node (ref "D8") (pin "1") (pinfunction "A_1") (pintype "passive"))
      (node (ref "R15") (pin "1") (pinfunction "1_1") (pintype "passive"))
    )
    (net (code "34") (name "Net-(D8-K)") (class "Default")
      (node (ref "D8") (pin "2") (pinfunction "K_2") (pintype "passive"))
      (node (ref "P4") (pin "1") (pinfunction "5_1") (pintype "passive"))
      (node (ref "Q11") (pin "3") (pinfunction "S_3") (pintype "passive"))
      (node (ref "R26") (pin "1") (pinfunction "1_1") (pintype "passive"))
      (node (ref "R54") (pin "2") (pinfunction "2_2") (pintype "passive"))
    )
    (net (code "35") (name "Net-(D9-A)") (class "Default")
      (node (ref "D9") (pin "1") (pinfunction "A_1") (pintype "passive"))
      (node (ref "R22") (pin "1") (pinfunction "1_1") (pintype "passive"))
    )
    (net (code "36") (name "Net-(D9-K)") (class "Default")
      (node (ref "D9") (pin "2") (pinfunction "K_2") (pintype "passive"))
      (node (ref "P4") (pin "2") (pinfunction "4_2") (pintype "passive"))
      (node (ref "Q5") (pin "3") (pinfunction "S_3") (pintype "passive"))
      (node (ref "R34") (pin "1") (pinfunction "1_1") (pintype "passive"))
      (node (ref "R56") (pin "2") (pinfunction "2_2") (pintype "passive"))
    )
    (net (code "37") (name "Net-(D10-A)") (class "Default")
      (node (ref "D10") (pin "1") (pinfunction "A_1") (pintype "passive"))
      (node (ref "R16") (pin "1") (pinfunction "1_1") (pintype "passive"))
    )
    (net (code "38") (name "Net-(D10-K)") (class "Default")
      (node (ref "D10") (pin "2") (pinfunction "K_2") (pintype "passive"))
      (node (ref "P4") (pin "4") (pinfunction "3_4") (pintype "passive"))
      (node (ref "Q12") (pin "3") (pinfunction "S_3") (pintype "passive"))
      (node (ref "R27") (pin "1") (pinfunction "1_1") (pintype "passive"))
      (node (ref "R58") (pin "2") (pinfunction "2_2") (pintype "passive"))
    )
    (net (code "39") (name "Net-(D11-A)") (class "Default")
      (node (ref "D11") (pin "1") (pinfunction "A_1") (pintype "passive"))
      (node (ref "R28") (pin "1") (pinfunction "1_1") (pintype "passive"))
    )
    (net (code "40") (name "Net-(D11-K)") (class "Default")
      (node (ref "D11") (pin "2") (pinfunction "K_2") (pintype "passive"))
      (node (ref "P4") (pin "6") (pinfunction "2_6") (pintype "passive"))
      (node (ref "Q6") (pin "3") (pinfunction "S_3") (pintype "passive"))
      (node (ref "R35") (pin "1") (pinfunction "1_1") (pintype "passive"))
      (node (ref "R60") (pin "2") (pinfunction "2_2") (pintype "passive"))
    )
    (net (code "41") (name "Net-(D12-A)") (class "Default")
      (node (ref "D12") (pin "1") (pinfunction "A_1") (pintype "passive"))
      (node (ref "R17") (pin "1") (pinfunction "1_1") (pintype "passive"))
    )
    (net (code "42") (name "Net-(D13-A)") (class "Default")
      (node (ref "D13") (pin "1") (pinfunction "A_1") (pintype "passive"))
      (node (ref "R66") (pin "2") (pinfunction "2_2") (pintype "passive"))
    )
    (net (code "43") (name "Net-(Q1-D)") (class "Default")
      (node (ref "Q1") (pin "2") (pinfunction "D_2") (pintype "passive"))
      (node (ref "R12") (pin "1") (pinfunction "1_1") (pintype "passive"))
      (node (ref "R23") (pin "2") (pinfunction "2_2") (pintype "passive"))
    )
    (net (code "44") (name "Net-(Q1-G)") (class "Default")
      (node (ref "Q1") (pin "1") (pinfunction "G_1") (pintype "passive"))
      (node (ref "R41") (pin "2") (pinfunction "2_2") (pintype "passive"))
    )
    (net (code "45") (name "Net-(Q2-D)") (class "Default")
      (node (ref "Q2") (pin "2") (pinfunction "D_2") (pintype "passive"))
      (node (ref "R13") (pin "2") (pinfunction "2_2") (pintype "passive"))
      (node (ref "R24") (pin "2") (pinfunction "2_2") (pintype "passive"))
    )
    (net (code "46") (name "Net-(Q2-G)") (class "Default")
      (node (ref "Q2") (pin "1") (pinfunction "G_1") (pintype "passive"))
      (node (ref "R45") (pin "2") (pinfunction "2_2") (pintype "passive"))
    )
    (net (code "47") (name "Net-(Q3-D)") (class "Default")
      (node (ref "Q3") (pin "2") (pinfunction "D_2") (pintype "passive"))
      (node (ref "R14") (pin "2") (pinfunction "2_2") (pintype "passive"))
      (node (ref "R25") (pin "2") (pinfunction "2_2") (pintype "passive"))
    )
    (net (code "48") (name "Net-(Q3-G)") (class "Default")
      (node (ref "Q3") (pin "1") (pinfunction "G_1") (pintype "passive"))
      (node (ref "R49") (pin "2") (pinfunction "2_2") (pintype "passive"))
    )
    (net (code "49") (name "Net-(Q4-D)") (class "Default")
      (node (ref "Q4") (pin "2") (pinfunction "D_2") (pintype "passive"))
      (node (ref "R15") (pin "2") (pinfunction "2_2") (pintype "passive"))
      (node (ref "R26") (pin "2") (pinfunction "2_2") (pintype "passive"))
    )
    (net (code "50") (name "Net-(Q4-G)") (class "Default")
      (node (ref "Q4") (pin "1") (pinfunction "G_1") (pintype "passive"))
      (node (ref "R53") (pin "2") (pinfunction "2_2") (pintype "passive"))
    )
    (net (code "51") (name "Net-(Q5-D)") (class "Default")
      (node (ref "Q5") (pin "2") (pinfunction "D_2") (pintype "passive"))
      (node (ref "R16") (pin "2") (pinfunction "2_2") (pintype "passive"))
      (node (ref "R27") (pin "2") (pinfunction "2_2") (pintype "passive"))
    )
    (net (code "52") (name "Net-(Q5-G)") (class "Default")
      (node (ref "Q5") (pin "1") (pinfunction "G_1") (pintype "passive"))
      (node (ref "R57") (pin "2") (pinfunction "2_2") (pintype "passive"))
    )
    (net (code "53") (name "Net-(Q6-D)") (class "Default")
      (node (ref "Q6") (pin "2") (pinfunction "D_2") (pintype "passive"))
      (node (ref "R17") (pin "2") (pinfunction "2_2") (pintype "passive"))
      (node (ref "R29") (pin "2") (pinfunction "2_2") (pintype "passive"))
    )
    (net (code "54") (name "Net-(Q6-G)") (class "Default")
      (node (ref "Q6") (pin "1") (pinfunction "G_1") (pintype "passive"))
      (node (ref "R61") (pin "2") (pinfunction "2_2") (pintype "passive"))
    )
    (net (code "55") (name "Net-(Q7-D)") (class "Default")
      (node (ref "Q7") (pin "2") (pinfunction "D_2") (pintype "passive"))
      (node (ref "R18") (pin "2") (pinfunction "2_2") (pintype "passive"))
      (node (ref "R30") (pin "2") (pinfunction "2_2") (pintype "passive"))
    )
    (net (code "56") (name "Net-(Q7-G)") (class "Default")
      (node (ref "Q7") (pin "1") (pinfunction "G_1") (pintype "passive"))
      (node (ref "R39") (pin "2") (pinfunction "2_2") (pintype "passive"))
    )
    (net (code "57") (name "Net-(Q8-D)") (class "Default")
      (node (ref "Q8") (pin "2") (pinfunction "D_2") (pintype "passive"))
      (node (ref "R19") (pin "2") (pinfunction "2_2") (pintype "passive"))
      (node (ref "R31") (pin "2") (pinfunction "2_2") (pintype "passive"))
    )
    (net (code "58") (name "Net-(Q8-G)") (class "Default")
      (node (ref "Q8") (pin "1") (pinfunction "G_1") (pintype "passive"))
      (node (ref "R43") (pin "2") (pinfunction "2_2") (pintype "passive"))
    )
    (net (code "59") (name "Net-(Q9-D)") (class "Default")
      (node (ref "Q9") (pin "2") (pinfunction "D_2") (pintype "passive"))
      (node (ref "R20") (pin "2") (pinfunction "2_2") (pintype "passive"))
      (node (ref "R32") (pin "2") (pinfunction "2_2") (pintype "passive"))
    )
    (net (code "60") (name "Net-(Q9-G)") (class "Default")
      (node (ref "Q9") (pin "1") (pinfunction "G_1") (pintype "passive"))
      (node (ref "R47") (pin "2") (pinfunction "2_2") (pintype "passive"))
    )
    (net (code "61") (name "Net-(Q10-D)") (class "Default")
      (node (ref "Q10") (pin "2") (pinfunction "D_2") (pintype "passive"))
      (node (ref "R21") (pin "2") (pinfunction "2_2") (pintype "passive"))
      (node (ref "R33") (pin "2") (pinfunction "2_2") (pintype "passive"))
    )
    (net (code "62") (name "Net-(Q10-G)") (class "Default")
      (node (ref "Q10") (pin "1") (pinfunction "G_1") (pintype "passive"))
      (node (ref "R51") (pin "2") (pinfunction "2_2") (pintype "passive"))
    )
    (net (code "63") (name "Net-(Q11-D)") (class "Default")
      (node (ref "Q11") (pin "2") (pinfunction "D_2") (pintype "passive"))
      (node (ref "R22") (pin "2") (pinfunction "2_2") (pintype "passive"))
      (node (ref "R34") (pin "2") (pinfunction "2_2") (pintype "passive"))
    )
    (net (code "64") (name "Net-(Q11-G)") (class "Default")
      (node (ref "Q11") (pin "1") (pinfunction "G_1") (pintype "passive"))
      (node (ref "R55") (pin "2") (pinfunction "2_2") (pintype "passive"))
    )
    (net (code "65") (name "Net-(Q12-D)") (class "Default")
      (node (ref "Q12") (pin "2") (pinfunction "D_2") (pintype "passive"))
      (node (ref "R28") (pin "2") (pinfunction "2_2") (pintype "passive"))
      (node (ref "R35") (pin "2") (pinfunction "2_2") (pintype "passive"))
    )
    (net (code "66") (name "Net-(Q12-G)") (class "Default")
      (node (ref "Q12") (pin "1") (pinfunction "G_1") (pintype "passive"))
      (node (ref "R59") (pin "2") (pinfunction "2_2") (pintype "passive"))
    )
    (net (code "67") (name "Net-(R63-Pad2)") (class "Default")
      (node (ref "R63") (pin "2") (pinfunction "2_2") (pintype "passive"))
      (node (ref "R65") (pin "2") (pinfunction "2_2") (pintype "passive"))
      (node (ref "U2") (pin "4") (pinfunction "IPA_4") (pintype "passive"))
    )
    (net (code "68") (name "Net-(R64-Pad2)") (class "Default")
      (node (ref "R64") (pin "2") (pinfunction "2_2") (pintype "passive"))
      (node (ref "R65") (pin "1") (pinfunction "1_1") (pintype "passive"))
      (node (ref "U2") (pin "3") (pinfunction "IMA_3") (pintype "passive"))
    )
    (net (code "69") (name "Net-(T1-Pad2)") (class "Default")
      (node (ref "T1") (pin "2") (pintype "passive"))
      (node (ref "T2") (pin "4") (pintype "passive"))
      (node (ref "U2") (pin "2") (pinfunction "IMA_2") (pintype "passive"))
    )
    (net (code "70") (name "Net-(T1-Pad3)") (class "Default")
      (node (ref "T1") (pin "3") (pintype "passive"))
      (node (ref "T2") (pin "2") (pintype "passive"))
      (node (ref "U2") (pin "1") (pinfunction "IPA_1") (pintype "passive"))
    )
    (net (code "71") (name "Net-(U1-BOOST)") (class "Default")
      (node (ref "C5") (pin "2") (pinfunction "2_2") (pintype "passive"))
      (node (ref "U1") (pin "7") (pinfunction "BOOST_7") (pintype "passive"))
    )
    (net (code "72") (name "Net-(U1-FB)") (class "Default")
      (node (ref "C4") (pin "1") (pinfunction "1_1") (pintype "passive"))
      (node (ref "R36") (pin "1") (pinfunction "1_1") (pintype "passive"))
      (node (ref "R37") (pin "2") (pinfunction "2_2") (pintype "passive"))
      (node (ref "U1") (pin "1") (pinfunction "FB_1") (pintype "passive"))
    )
    (net (code "73") (name "Net-(U1-RT)") (class "Default")
      (node (ref "R11") (pin "2") (pinfunction "2_2") (pintype "passive"))
      (node (ref "U1") (pin "10") (pinfunction "RT_10") (pintype "passive"))
    )
    (net (code "74") (name "Net-(U1-SW)") (class "Default")
      (node (ref "C5") (pin "1") (pinfunction "1_1") (pintype "passive"))
      (node (ref "L1") (pin "1") (pinfunction "1_1") (pintype "passive"))
      (node (ref "U1") (pin "6") (pinfunction "SW_6") (pintype "passive"))
    )
    (net (code "75") (name "Net-(U3-C0)") (class "Default")
      (node (ref "C19") (pin "2") (pinfunction "2_2") (pintype "passive"))
      (node (ref "R62") (pin "1") (pinfunction "1_1") (pintype "passive"))
      (node (ref "U3") (pin "26") (pinfunction "C0_26") (pintype "passive"))
    )
    (net (code "76") (name "Net-(U3-C1)") (class "Default")
      (node (ref "C18") (pin "2") (pinfunction "2_2") (pintype "passive"))
      (node (ref "R60") (pin "1") (pinfunction "1_1") (pintype "passive"))
      (node (ref "U3") (pin "24") (pinfunction "C1_24") (pintype "passive"))
    )
    (net (code "77") (name "Net-(U3-C2)") (class "Default")
      (node (ref "C17") (pin "2") (pinfunction "2_2") (pintype "passive"))
      (node (ref "R58") (pin "1") (pinfunction "1_1") (pintype "passive"))
      (node (ref "U3") (pin "22") (pinfunction "C2_22") (pintype "passive"))
    )
    (net (code "78") (name "Net-(U3-C3)") (class "Default")
      (node (ref "C16") (pin "2") (pinfunction "2_2") (pintype "passive"))
      (node (ref "R56") (pin "1") (pinfunction "1_1") (pintype "passive"))
      (node (ref "U3") (pin "20") (pinfunction "C3_20") (pintype "passive"))
    )
    (net (code "79") (name "Net-(U3-C4)") (class "Default")
      (node (ref "C15") (pin "2") (pinfunction "2_2") (pintype "passive"))
      (node (ref "R54") (pin "1") (pinfunction "1_1") (pintype "passive"))
      (node (ref "U3") (pin "18") (pinfunction "C4_18") (pintype "passive"))
    )
    (net (code "80") (name "Net-(U3-C5)") (class "Default")
      (node (ref "C14") (pin "2") (pinfunction "2_2") (pintype "passive"))
      (node (ref "R52") (pin "1") (pinfunction "1_1") (pintype "passive"))
      (node (ref "U3") (pin "16") (pinfunction "C5_16") (pintype "passive"))
    )
    (net (code "81") (name "Net-(U3-C6)") (class "Default")
      (node (ref "C13") (pin "2") (pinfunction "2_2") (pintype "passive"))
      (node (ref "R50") (pin "1") (pinfunction "1_1") (pintype "passive"))
      (node (ref "U3") (pin "14") (pinfunction "C6_14") (pintype "passive"))
    )
    (net (code "82") (name "Net-(U3-C7)") (class "Default")
      (node (ref "C12") (pin "2") (pinfunction "2_2") (pintype "passive"))
      (node (ref "R48") (pin "1") (pinfunction "1_1") (pintype "passive"))
      (node (ref "U3") (pin "12") (pinfunction "C7_12") (pintype "passive"))
    )
    (net (code "83") (name "Net-(U3-C8)") (class "Default")
      (node (ref "C11") (pin "2") (pinfunction "2_2") (pintype "passive"))
      (node (ref "R46") (pin "1") (pinfunction "1_1") (pintype "passive"))
      (node (ref "U3") (pin "10") (pinfunction "C8_10") (pintype "passive"))
    )
    (net (code "84") (name "Net-(U3-C9)") (class "Default")
      (node (ref "C10") (pin "2") (pinfunction "2_2") (pintype "passive"))
      (node (ref "R44") (pin "1") (pinfunction "1_1") (pintype "passive"))
      (node (ref "U3") (pin "8") (pinfunction "C9_8") (pintype "passive"))
    )
    (net (code "85") (name "Net-(U3-C10)") (class "Default")
      (node (ref "C9") (pin "2") (pinfunction "2_2") (pintype "passive"))
      (node (ref "R42") (pin "1") (pinfunction "1_1") (pintype "passive"))
      (node (ref "U3") (pin "6") (pinfunction "C10_6") (pintype "passive"))
    )
    (net (code "86") (name "Net-(U3-C11)") (class "Default")
      (node (ref "C8") (pin "2") (pinfunction "2_2") (pintype "passive"))
      (node (ref "R40") (pin "1") (pinfunction "1_1") (pintype "passive"))
      (node (ref "U3") (pin "4") (pinfunction "C11_4") (pintype "passive"))
    )
    (net (code "87") (name "Net-(U3-C12)") (class "Default")
      (node (ref "C7") (pin "2") (pinfunction "2_2") (pintype "passive"))
      (node (ref "R38") (pin "1") (pinfunction "1_1") (pintype "passive"))
      (node (ref "U3") (pin "2") (pinfunction "C12_2") (pintype "passive"))
    )
    (net (code "88") (name "Net-(U3-S1)") (class "Default")
      (node (ref "R61") (pin "1") (pinfunction "1_1") (pintype "passive"))
      (node (ref "U3") (pin "25") (pinfunction "S1_25") (pintype "passive"))
    )
    (net (code "89") (name "Net-(U3-S2)") (class "Default")
      (node (ref "R59") (pin "1") (pinfunction "1_1") (pintype "passive"))
      (node (ref "U3") (pin "23") (pinfunction "S2_23") (pintype "passive"))
    )
    (net (code "90") (name "Net-(U3-S3)") (class "Default")
      (node (ref "R57") (pin "1") (pinfunction "1_1") (pintype "passive"))
      (node (ref "U3") (pin "21") (pinfunction "S3_21") (pintype "passive"))
    )
    (net (code "91") (name "Net-(U3-S4)") (class "Default")
      (node (ref "R55") (pin "1") (pinfunction "1_1") (pintype "passive"))
      (node (ref "U3") (pin "19") (pinfunction "S4_19") (pintype "passive"))
    )
    (net (code "92") (name "Net-(U3-S5)") (class "Default")
      (node (ref "R53") (pin "1") (pinfunction "1_1") (pintype "passive"))
      (node (ref "U3") (pin "17") (pinfunction "S5_17") (pintype "passive"))
    )
    (net (code "93") (name "Net-(U3-S6)") (class "Default")
      (node (ref "R51") (pin "1") (pinfunction "1_1") (pintype "passive"))
      (node (ref "U3") (pin "15") (pinfunction "S6_15") (pintype "passive"))
    )
    (net (code "94") (name "Net-(U3-S7)") (class "Default")
      (node (ref "R49") (pin "1") (pinfunction "1_1") (pintype "passive"))
      (node (ref "U3") (pin "13") (pinfunction "S7_13") (pintype "passive"))
    )
    (net (code "95") (name "Net-(U3-S8)") (class "Default")
      (node (ref "R47") (pin "1") (pinfunction "1_1") (pintype "passive"))
      (node (ref "U3") (pin "11") (pinfunction "S8_11") (pintype "passive"))
    )
    (net (code "96") (name "Net-(U3-S9)") (class "Default")
      (node (ref "R45") (pin "1") (pinfunction "1_1") (pintype "passive"))
      (node (ref "U3") (pin "9") (pinfunction "S9_9") (pintype "passive"))
    )
    (net (code "97") (name "Net-(U3-S10)") (class "Default")
      (node (ref "R43") (pin "1") (pinfunction "1_1") (pintype "passive"))
      (node (ref "U3") (pin "7") (pinfunction "S10_7") (pintype "passive"))
    )
    (net (code "98") (name "Net-(U3-S11)") (class "Default")
      (node (ref "R41") (pin "1") (pinfunction "1_1") (pintype "passive"))
      (node (ref "U3") (pin "5") (pinfunction "S11_5") (pintype "passive"))
    )
    (net (code "99") (name "Net-(U3-S12)") (class "Default")
      (node (ref "R39") (pin "1") (pinfunction "1_1") (pintype "passive"))
      (node (ref "U3") (pin "3") (pinfunction "S12_3") (pintype "passive"))
    )
    (net (code "100") (name "Net-(U3-SDI(ICMP))") (class "Default")
      (node (ref "R67") (pin "2") (pinfunction "2_2") (pintype "passive"))
      (node (ref "R69") (pin "1") (pinfunction "1_1") (pintype "passive"))
      (node (ref "U3") (pin "43") (pinfunction "SDI(ICMP)_43") (pintype "passive"))
    )
    (net (code "101") (name "Net-(U3-SDO(IBIAS))") (class "Default")
      (node (ref "R67") (pin "1") (pinfunction "1_1") (pintype "passive"))
      (node (ref "U3") (pin "44") (pinfunction "SDO(IBIAS)_44") (pintype "passive"))
    )
    (net (code "102") (name "Net-(U3-V-)") (class "Default")
      (node (ref "C21") (pin "2") (pinfunction "2_2") (pintype "passive"))
      (node (ref "U3") (pin "30") (pinfunction "V-**_30") (pintype "passive"))
      (node (ref "U3") (pin "31") (pinfunction "V-_31") (pintype "passive"))
    )
    (net (code "103") (name "Net-(U3-WDT)") (class "Default")
      (node (ref "R68") (pin "1") (pinfunction "1_1") (pintype "passive"))
      (node (ref "U3") (pin "39") (pinfunction "WDT_39") (pintype "passive"))
    )
    (net (code "104") (name "unconnected-(P3-Pad1)") (class "Default")
      (node (ref "P3") (pin "1") (pinfunction "1_1") (pintype "passive"))
    )
    (net (code "105") (name "unconnected-(P3-Pad2)") (class "Default")
      (node (ref "P3") (pin "2") (pinfunction "2_2") (pintype "passive"))
    )
    (net (code "106") (name "unconnected-(R63-Pad1)") (class "Default")
      (node (ref "R63") (pin "1") (pinfunction "1_1") (pintype "passive"))
    )
    (net (code "107") (name "unconnected-(R64-Pad1)") (class "Default")
      (node (ref "R64") (pin "1") (pinfunction "1_1") (pintype "passive"))
    )
    (net (code "108") (name "unconnected-(U1-PG-Pad9)") (class "Default")
      (node (ref "U1") (pin "9") (pinfunction "PG_9") (pintype "passive"))
    )
    (net (code "109") (name "unconnected-(U3-VREF1-Pad35)") (class "Default")
      (node (ref "U3") (pin "35") (pinfunction "VREF1_35") (pintype "passive"))
    )
  )
)
